# MainBoard_v5.net
KiCad netlist of a schematic drawn in EAGLE
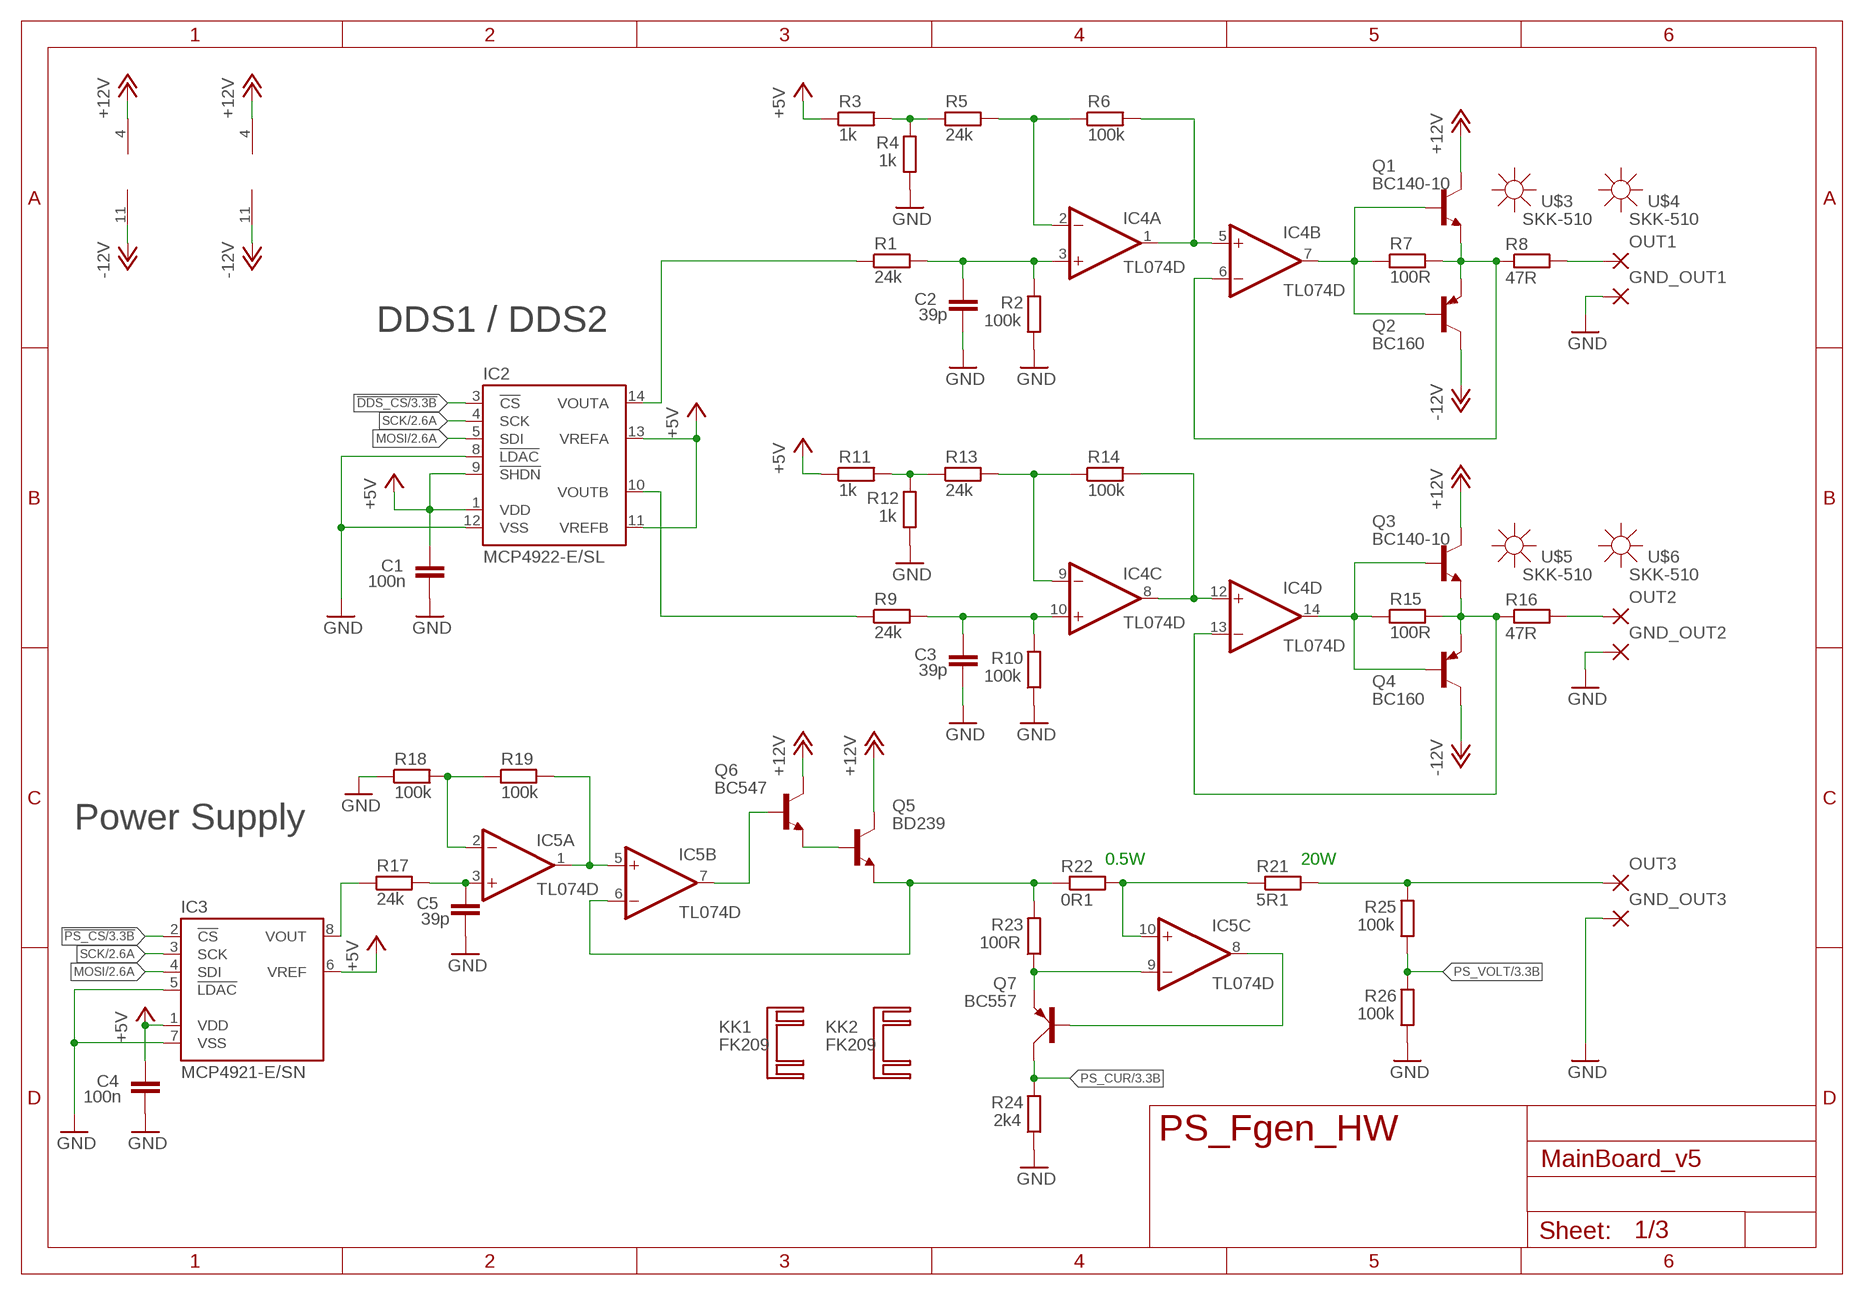
[diagram p0: schematic, sheet 1]
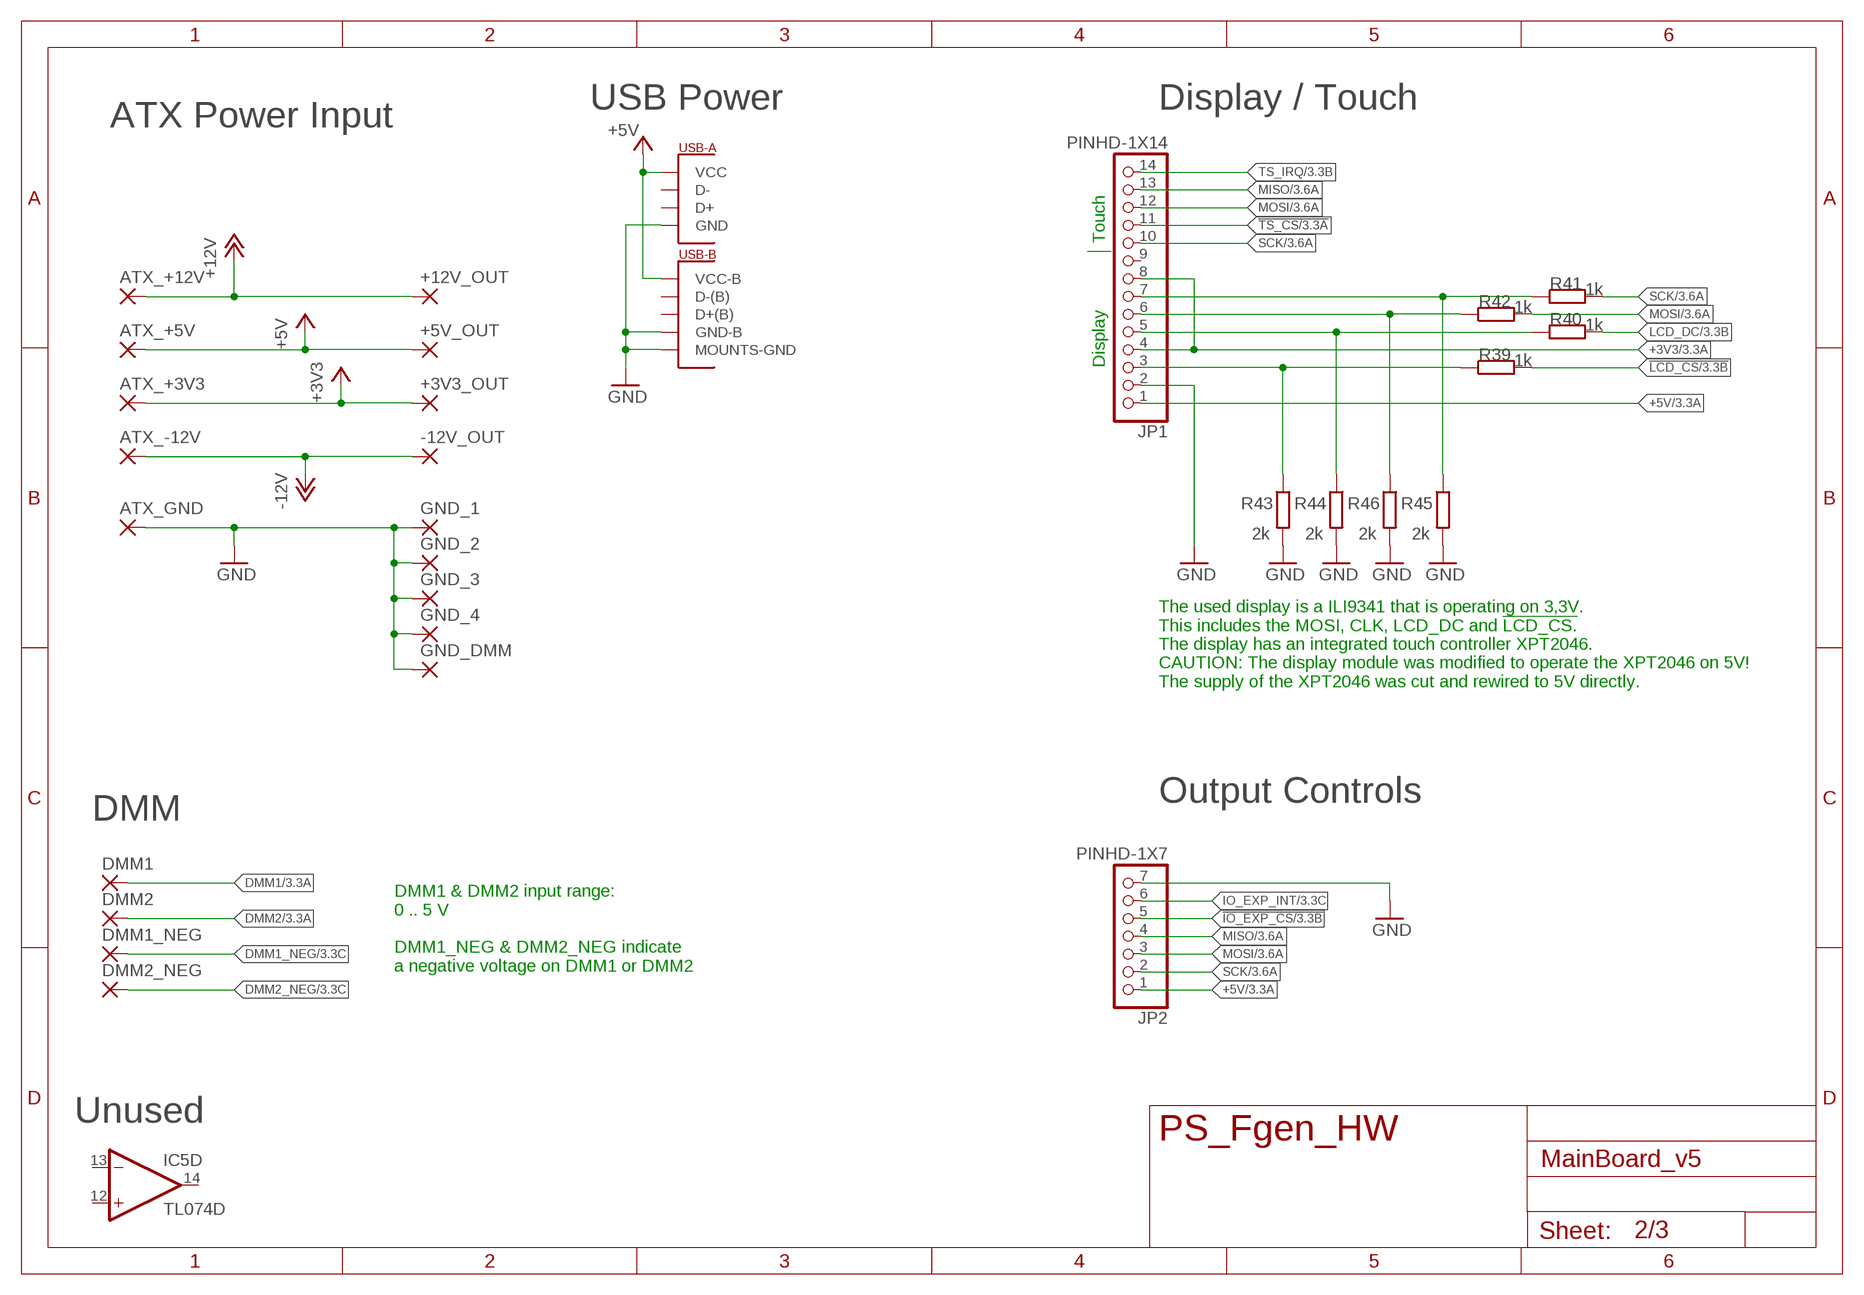
[diagram p1: schematic, sheet 2]
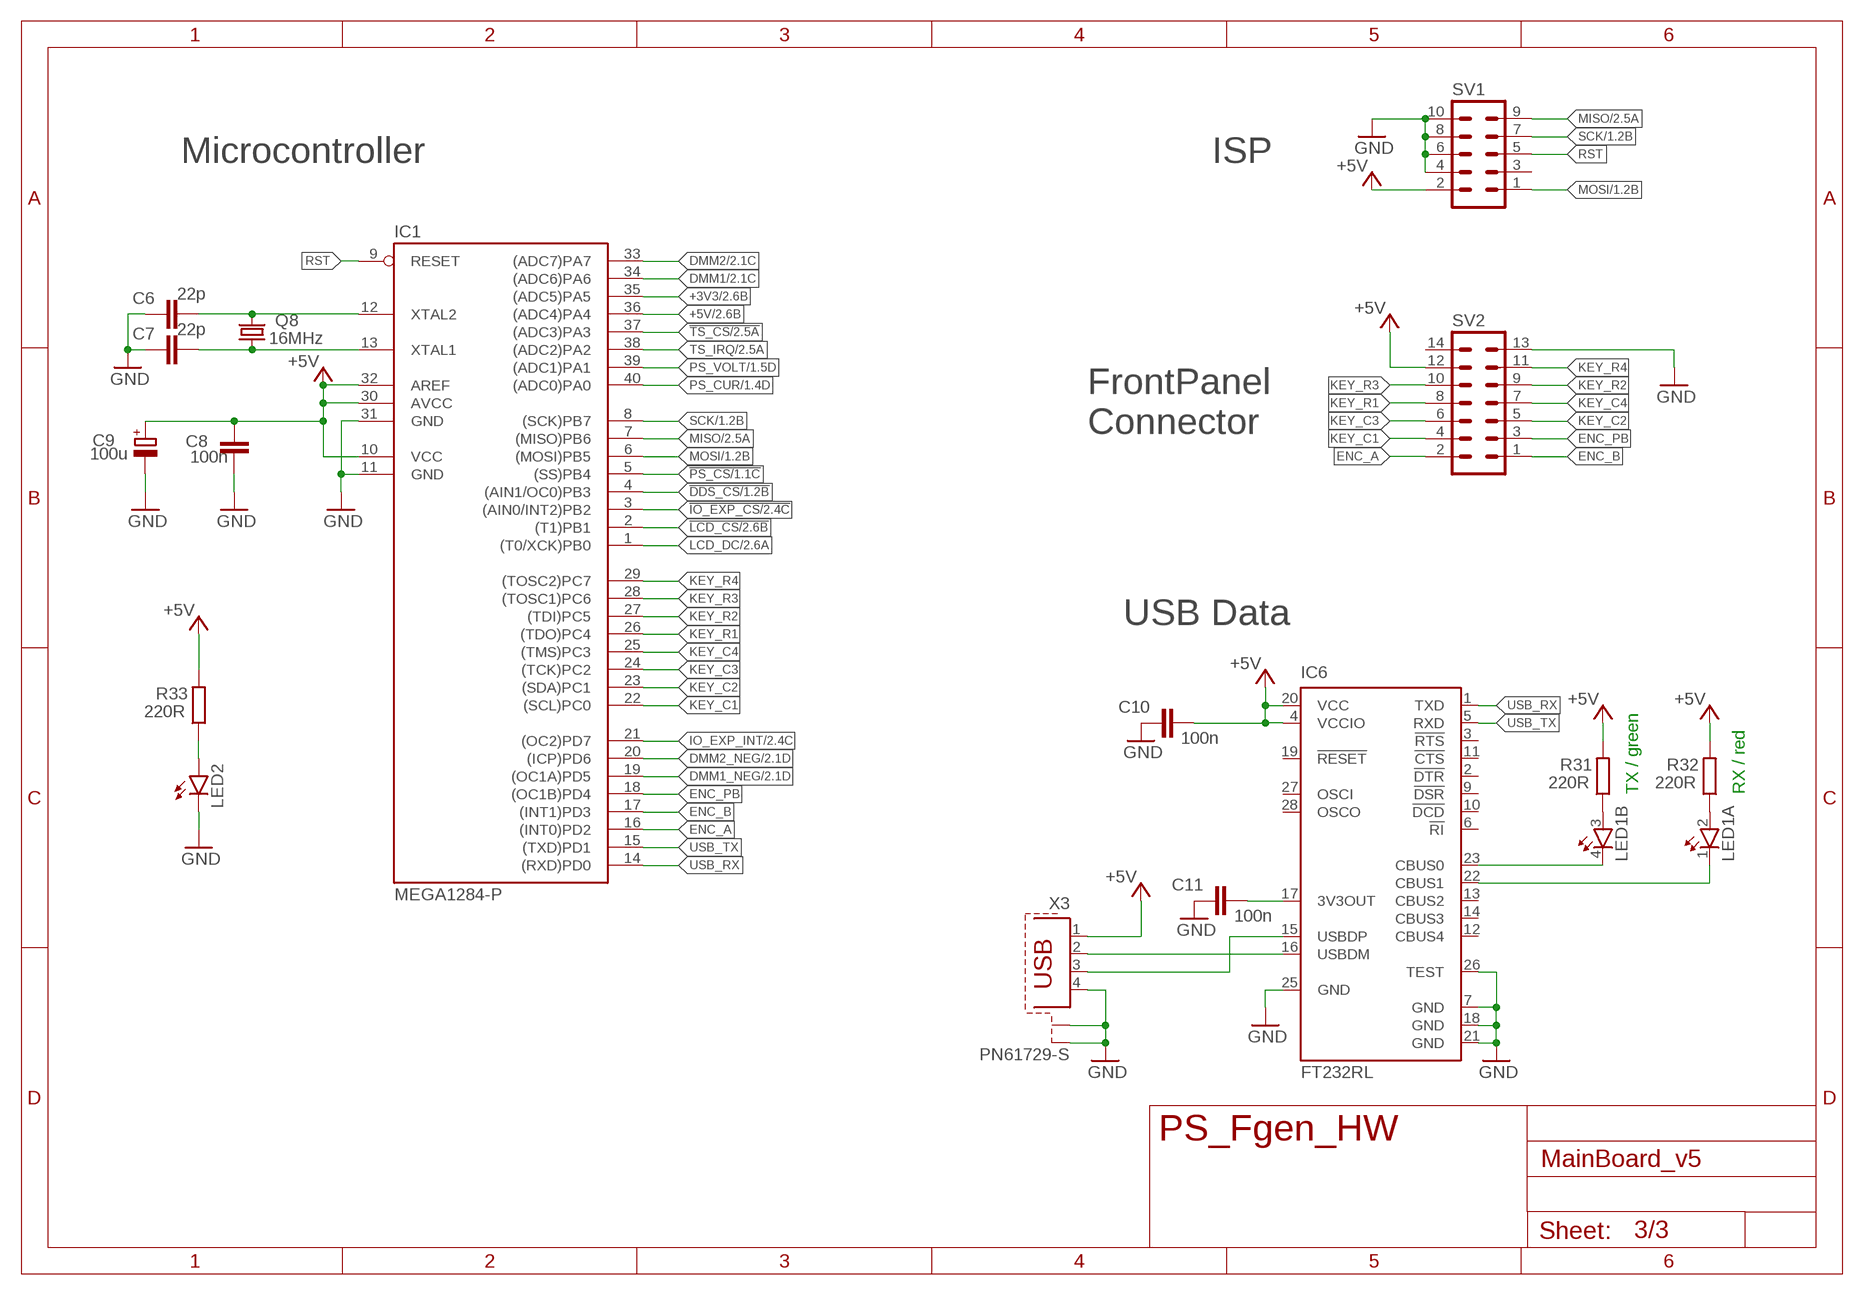
[diagram p2: schematic, sheet 3]

(export (version "E")
  (design (tool "Eeschema 10.0.6"))
  (components
    (comp (ref "C6")
      (value "22p")
      (footprint "eagle-import:C0805")
      (libsource (lib "eagle-import") (part "C-EUC0805"))
    )
    (comp (ref "C7")
      (value "22p")
      (footprint "eagle-import:C0805")
      (libsource (lib "eagle-import") (part "C-EUC0805"))
    )
    (comp (ref "C8")
      (value "100n")
      (footprint "eagle-import:C0805")
      (libsource (lib "eagle-import") (part "C-EUC0805"))
    )
    (comp (ref "C9")
      (value "100u")
      (footprint "eagle-import:PANASONIC_D")
      (libsource (lib "eagle-import") (part "CPOL-EUD"))
    )
    (comp (ref "C10")
      (value "100n")
      (footprint "eagle-import:C0805")
      (libsource (lib "eagle-import") (part "C-EUC0805"))
    )
    (comp (ref "C11")
      (value "100n")
      (footprint "eagle-import:C0805")
      (libsource (lib "eagle-import") (part "C-EUC0805"))
    )
    (comp (ref "IC1")
      (value "MEGA1284-P")
      (footprint "eagle-import:DIL40")
      (fields (field (name "MPN") "ATMEGA16-16PU"))
      (libsource (lib "eagle-import") (part "MEGA16-P"))
    )
    (comp (ref "IC6")
      (value "FT232RL")
      (footprint "eagle-import:SSOP28")
      (libsource (lib "eagle-import") (part "FT232RL"))
    )
    (comp (ref "LED1")
      (value "TOPLED-2--")
      (footprint "eagle-import:P-LCC-4-2")
      (libsource (lib "eagle-import") (part "TOPLED-2--"))
    )
    (comp (ref "LED2")
      (value "LEDCHIP-LED0805")
      (footprint "eagle-import:CHIP-LED0805")
      (libsource (lib "eagle-import") (part "LEDCHIP-LED0805"))
    )
    (comp (ref "Q8")
      (value "16MHz")
      (footprint "eagle-import:HC49_S")
      (libsource (lib "eagle-import") (part "CRYSTALHC49S"))
    )
    (comp (ref "R31")
      (value "220R")
      (footprint "eagle-import:R0805")
      (libsource (lib "eagle-import") (part "R-EU_R0805"))
    )
    (comp (ref "R32")
      (value "220R")
      (footprint "eagle-import:R0805")
      (libsource (lib "eagle-import") (part "R-EU_R0805"))
    )
    (comp (ref "R33")
      (value "220R")
      (footprint "eagle-import:R0805")
      (libsource (lib "eagle-import") (part "R-EU_R0805"))
    )
    (comp (ref "SV1")
      (value "ML10")
      (footprint "eagle-import:ML10")
      (libsource (lib "eagle-import") (part "ML10"))
    )
    (comp (ref "SV2")
      (value "ML14")
      (footprint "eagle-import:ML14")
      (libsource (lib "eagle-import") (part "ML14"))
    )
    (comp (ref "X3")
      (value "PN61729-S")
      (footprint "eagle-import:PN61729-S")
      (libsource (lib "eagle-import") (part "PN61729-S"))
    )
    (comp (ref "C1")
      (value "100n")
      (footprint "eagle-import:C0805")
      (libsource (lib "eagle-import") (part "C-EUC0805"))
    )
    (comp (ref "C2")
      (value "39p")
      (footprint "eagle-import:C0805")
      (libsource (lib "eagle-import") (part "C-EUC0805"))
    )
    (comp (ref "C3")
      (value "39p")
      (footprint "eagle-import:C0805")
      (libsource (lib "eagle-import") (part "C-EUC0805"))
    )
    (comp (ref "C4")
      (value "100n")
      (footprint "eagle-import:C0805")
      (libsource (lib "eagle-import") (part "C-EUC0805"))
    )
    (comp (ref "C5")
      (value "39p")
      (footprint "eagle-import:C0805")
      (libsource (lib "eagle-import") (part "C-EUC0805"))
    )
    (comp (ref "GND_OUT1")
      (value "2,54/1,0")
      (footprint "eagle-import:2,54_1,0")
      (libsource (lib "eagle-import") (part "2,54/1,0"))
    )
    (comp (ref "GND_OUT2")
      (value "2,54/1,0")
      (footprint "eagle-import:2,54_1,0")
      (libsource (lib "eagle-import") (part "2,54/1,0"))
    )
    (comp (ref "GND_OUT3")
      (value "2,54/1,0")
      (footprint "eagle-import:2,54_1,0")
      (libsource (lib "eagle-import") (part "2,54/1,0"))
    )
    (comp (ref "IC2")
      (value "MCP4922-E/SL")
      (footprint "eagle-import:SO14")
      (libsource (lib "eagle-import") (part "MCP4922-E/SL"))
    )
    (comp (ref "IC3")
      (value "MCP4921-E/SN")
      (footprint "eagle-import:SO08")
      (libsource (lib "eagle-import") (part "MCP4921-E/SN"))
    )
    (comp (ref "IC4")
      (value "TL074D")
      (footprint "eagle-import:SO14")
      (libsource (lib "eagle-import") (part "TL074D"))
    )
    (comp (ref "IC5")
      (value "TL074D")
      (footprint "eagle-import:SO14")
      (libsource (lib "eagle-import") (part "TL074D"))
    )
    (comp (ref "KK1")
      (value "FK209")
      (footprint "eagle-import:FK209")
      (libsource (lib "eagle-import") (part "FK209"))
    )
    (comp (ref "KK2")
      (value "FK209")
      (footprint "eagle-import:FK209")
      (libsource (lib "eagle-import") (part "FK209"))
    )
    (comp (ref "OUT1")
      (value "2,54/1,0")
      (footprint "eagle-import:2,54_1,0")
      (libsource (lib "eagle-import") (part "2,54/1,0"))
    )
    (comp (ref "OUT2")
      (value "2,54/1,0")
      (footprint "eagle-import:2,54_1,0")
      (libsource (lib "eagle-import") (part "2,54/1,0"))
    )
    (comp (ref "OUT3")
      (value "2,54/1,0")
      (footprint "eagle-import:2,54_1,0")
      (libsource (lib "eagle-import") (part "2,54/1,0"))
    )
    (comp (ref "Q1")
      (value "BC140-10")
      (footprint "eagle-import:TO39")
      (libsource (lib "eagle-import") (part "BC140-10"))
    )
    (comp (ref "Q2")
      (value "BC160")
      (footprint "eagle-import:TO39")
      (libsource (lib "eagle-import") (part "BC160"))
    )
    (comp (ref "Q3")
      (value "BC140-10")
      (footprint "eagle-import:TO39")
      (libsource (lib "eagle-import") (part "BC140-10"))
    )
    (comp (ref "Q4")
      (value "BC160")
      (footprint "eagle-import:TO39")
      (libsource (lib "eagle-import") (part "BC160"))
    )
    (comp (ref "Q5")
      (value "BD239")
      (footprint "eagle-import:CB-274")
      (libsource (lib "eagle-import") (part "BD239TO220BV"))
    )
    (comp (ref "Q6")
      (value "BC547")
      (footprint "eagle-import:TO92")
      (libsource (lib "eagle-import") (part "BC547"))
    )
    (comp (ref "Q7")
      (value "BC557")
      (footprint "eagle-import:SOT54A")
      (libsource (lib "eagle-import") (part "BC557"))
    )
    (comp (ref "R1")
      (value "24k")
      (footprint "eagle-import:R0805")
      (libsource (lib "eagle-import") (part "R-EU_R0805"))
    )
    (comp (ref "R2")
      (value "100k")
      (footprint "eagle-import:R0805")
      (libsource (lib "eagle-import") (part "R-EU_R0805"))
    )
    (comp (ref "R3")
      (value "1k")
      (footprint "eagle-import:R0805")
      (libsource (lib "eagle-import") (part "R-EU_R0805"))
    )
    (comp (ref "R4")
      (value "1k")
      (footprint "eagle-import:R0805")
      (libsource (lib "eagle-import") (part "R-EU_R0805"))
    )
    (comp (ref "R5")
      (value "24k")
      (footprint "eagle-import:R0805")
      (libsource (lib "eagle-import") (part "R-EU_R0805"))
    )
    (comp (ref "R6")
      (value "100k")
      (footprint "eagle-import:R0805")
      (libsource (lib "eagle-import") (part "R-EU_R0805"))
    )
    (comp (ref "R7")
      (value "100R")
      (footprint "eagle-import:R0805")
      (libsource (lib "eagle-import") (part "R-EU_R0805"))
    )
    (comp (ref "R8")
      (value "47R")
      (footprint "eagle-import:0411_15")
      (libsource (lib "eagle-import") (part "R-EU_0411/15"))
    )
    (comp (ref "R9")
      (value "24k")
      (footprint "eagle-import:R0805")
      (libsource (lib "eagle-import") (part "R-EU_R0805"))
    )
    (comp (ref "R10")
      (value "100k")
      (footprint "eagle-import:R0805")
      (libsource (lib "eagle-import") (part "R-EU_R0805"))
    )
    (comp (ref "R11")
      (value "1k")
      (footprint "eagle-import:R0805")
      (libsource (lib "eagle-import") (part "R-EU_R0805"))
    )
    (comp (ref "R12")
      (value "1k")
      (footprint "eagle-import:R0805")
      (libsource (lib "eagle-import") (part "R-EU_R0805"))
    )
    (comp (ref "R13")
      (value "24k")
      (footprint "eagle-import:R0805")
      (libsource (lib "eagle-import") (part "R-EU_R0805"))
    )
    (comp (ref "R14")
      (value "100k")
      (footprint "eagle-import:R0805")
      (libsource (lib "eagle-import") (part "R-EU_R0805"))
    )
    (comp (ref "R15")
      (value "100R")
      (footprint "eagle-import:R0805")
      (libsource (lib "eagle-import") (part "R-EU_R0805"))
    )
    (comp (ref "R16")
      (value "47R")
      (footprint "eagle-import:0411_15")
      (libsource (lib "eagle-import") (part "R-EU_0411/15"))
    )
    (comp (ref "R17")
      (value "24k")
      (footprint "eagle-import:R0805")
      (libsource (lib "eagle-import") (part "R-EU_R0805"))
    )
    (comp (ref "R18")
      (value "100k")
      (footprint "eagle-import:R0805")
      (libsource (lib "eagle-import") (part "R-EU_R0805"))
    )
    (comp (ref "R19")
      (value "100k")
      (footprint "eagle-import:R0805")
      (libsource (lib "eagle-import") (part "R-EU_R0805"))
    )
    (comp (ref "R21")
      (value "5R1")
      (footprint "eagle-import:0411_15")
      (libsource (lib "eagle-import") (part "R-EU_0411/15"))
    )
    (comp (ref "R22")
      (value "0R1")
      (footprint "eagle-import:0411_15")
      (libsource (lib "eagle-import") (part "R-EU_0411/15"))
    )
    (comp (ref "R23")
      (value "100R")
      (footprint "eagle-import:R0805")
      (libsource (lib "eagle-import") (part "R-EU_R0805"))
    )
    (comp (ref "R24")
      (value "2k4")
      (footprint "eagle-import:R0805")
      (libsource (lib "eagle-import") (part "R-EU_R0805"))
    )
    (comp (ref "R25")
      (value "100k")
      (footprint "eagle-import:R0805")
      (libsource (lib "eagle-import") (part "R-EU_R0805"))
    )
    (comp (ref "R26")
      (value "100k")
      (footprint "eagle-import:R0805")
      (libsource (lib "eagle-import") (part "R-EU_R0805"))
    )
    (comp (ref "U$3")
      (value "SKK-510")
      (footprint "eagle-import:SKK")
      (libsource (lib "eagle-import") (part "SKK-510"))
    )
    (comp (ref "U$4")
      (value "SKK-510")
      (footprint "eagle-import:SKK")
      (libsource (lib "eagle-import") (part "SKK-510"))
    )
    (comp (ref "U$5")
      (value "SKK-510")
      (footprint "eagle-import:SKK")
      (libsource (lib "eagle-import") (part "SKK-510"))
    )
    (comp (ref "U$6")
      (value "SKK-510")
      (footprint "eagle-import:SKK")
      (libsource (lib "eagle-import") (part "SKK-510"))
    )
    (comp (ref "+3V3_OUT")
      (value "2,54/1,0")
      (footprint "eagle-import:2,54_1,0")
      (libsource (lib "eagle-import") (part "2,54/1,0"))
    )
    (comp (ref "+5V_OUT")
      (value "2,54/1,0")
      (footprint "eagle-import:2,54_1,0")
      (libsource (lib "eagle-import") (part "2,54/1,0"))
    )
    (comp (ref "+12V_OUT")
      (value "2,54/1,0")
      (footprint "eagle-import:2,54_1,0")
      (libsource (lib "eagle-import") (part "2,54/1,0"))
    )
    (comp (ref "-12V_OUT")
      (value "2,54/1,0")
      (footprint "eagle-import:2,54_1,0")
      (libsource (lib "eagle-import") (part "2,54/1,0"))
    )
    (comp (ref "ATX_+3V3")
      (value "2,54/1,0")
      (footprint "eagle-import:2,54_1,0")
      (libsource (lib "eagle-import") (part "2,54/1,0"))
    )
    (comp (ref "ATX_+5V")
      (value "2,54/1,0")
      (footprint "eagle-import:2,54_1,0")
      (libsource (lib "eagle-import") (part "2,54/1,0"))
    )
    (comp (ref "ATX_+12V")
      (value "2,54/1,0")
      (footprint "eagle-import:2,54_1,0")
      (libsource (lib "eagle-import") (part "2,54/1,0"))
    )
    (comp (ref "ATX_-12V")
      (value "2,54/1,0")
      (footprint "eagle-import:2,54_1,0")
      (libsource (lib "eagle-import") (part "2,54/1,0"))
    )
    (comp (ref "ATX_GND")
      (value "2,54/1,0")
      (footprint "eagle-import:2,54_1,0")
      (libsource (lib "eagle-import") (part "2,54/1,0"))
    )
    (comp (ref "DMM1")
      (value "2,54/1,0")
      (footprint "eagle-import:2,54_1,0")
      (libsource (lib "eagle-import") (part "2,54/1,0"))
    )
    (comp (ref "DMM1_NEG")
      (value "2,54/1,0")
      (footprint "eagle-import:2,54_1,0")
      (libsource (lib "eagle-import") (part "2,54/1,0"))
    )
    (comp (ref "DMM2")
      (value "2,54/1,0")
      (footprint "eagle-import:2,54_1,0")
      (libsource (lib "eagle-import") (part "2,54/1,0"))
    )
    (comp (ref "DMM2_NEG")
      (value "2,54/1,0")
      (footprint "eagle-import:2,54_1,0")
      (libsource (lib "eagle-import") (part "2,54/1,0"))
    )
    (comp (ref "GND_1")
      (value "2,54/1,0")
      (footprint "eagle-import:2,54_1,0")
      (libsource (lib "eagle-import") (part "2,54/1,0"))
    )
    (comp (ref "GND_2")
      (value "2,54/1,0")
      (footprint "eagle-import:2,54_1,0")
      (libsource (lib "eagle-import") (part "2,54/1,0"))
    )
    (comp (ref "GND_3")
      (value "2,54/1,0")
      (footprint "eagle-import:2,54_1,0")
      (libsource (lib "eagle-import") (part "2,54/1,0"))
    )
    (comp (ref "GND_4")
      (value "2,54/1,0")
      (footprint "eagle-import:2,54_1,0")
      (libsource (lib "eagle-import") (part "2,54/1,0"))
    )
    (comp (ref "GND_DMM")
      (value "2,54/1,0")
      (footprint "eagle-import:2,54_1,0")
      (libsource (lib "eagle-import") (part "2,54/1,0"))
    )
    (comp (ref "JP1")
      (value "PINHD-1X14")
      (footprint "eagle-import:1X14")
      (libsource (lib "eagle-import") (part "PINHD-1X14"))
    )
    (comp (ref "JP2")
      (value "PINHD-1X7")
      (footprint "eagle-import:1X07")
      (libsource (lib "eagle-import") (part "PINHD-1X7"))
    )
    (comp (ref "R39")
      (value "1k")
      (footprint "eagle-import:R0805")
      (libsource (lib "eagle-import") (part "R-EU_R0805"))
    )
    (comp (ref "R40")
      (value "1k")
      (footprint "eagle-import:R0805")
      (libsource (lib "eagle-import") (part "R-EU_R0805"))
    )
    (comp (ref "R41")
      (value "1k")
      (footprint "eagle-import:R0805")
      (libsource (lib "eagle-import") (part "R-EU_R0805"))
    )
    (comp (ref "R42")
      (value "1k")
      (footprint "eagle-import:R0805")
      (libsource (lib "eagle-import") (part "R-EU_R0805"))
    )
    (comp (ref "R43")
      (value "2k")
      (footprint "eagle-import:R0805")
      (libsource (lib "eagle-import") (part "R-EU_R0805"))
    )
    (comp (ref "R44")
      (value "2k")
      (footprint "eagle-import:R0805")
      (libsource (lib "eagle-import") (part "R-EU_R0805"))
    )
    (comp (ref "R45")
      (value "2k")
      (footprint "eagle-import:R0805")
      (libsource (lib "eagle-import") (part "R-EU_R0805"))
    )
    (comp (ref "R46")
      (value "2k")
      (footprint "eagle-import:R0805")
      (libsource (lib "eagle-import") (part "R-EU_R0805"))
    )
    (comp (ref "U$2")
      (value "DUAL-PORT-USB-REC")
      (footprint "eagle-import:DUAL-PORT-USB")
      (libsource (lib "eagle-import") (part "DUAL-PORT-USB-REC"))
    )
  )
  (nets
    (net (code "1") (name "+3V3") (class "Default")
      (node (ref "+3V3_OUT") (pin "1") (pinfunction "P_1") (pintype "passive"))
      (node (ref "ATX_+3V3") (pin "1") (pinfunction "P_1") (pintype "passive"))
      (node (ref "IC1") (pin "35") (pinfunction "(ADC5)PA5_35") (pintype "bidirectional"))
      (node (ref "JP1") (pin "4") (pinfunction "4_4") (pintype "passive"))
      (node (ref "JP1") (pin "8") (pinfunction "8_8") (pintype "passive"))
    )
    (net (code "2") (name "+5V") (class "Default")
      (node (ref "+5V_OUT") (pin "1") (pinfunction "P_1") (pintype "passive"))
      (node (ref "ATX_+5V") (pin "1") (pinfunction "P_1") (pintype "passive"))
      (node (ref "C1") (pin "2") (pinfunction "2_2") (pintype "passive"))
      (node (ref "C10") (pin "1") (pinfunction "1_1") (pintype "passive"))
      (node (ref "C4") (pin "2") (pinfunction "2_2") (pintype "passive"))
      (node (ref "C8") (pin "2") (pinfunction "2_2") (pintype "passive"))
      (node (ref "C9") (pin "+") (pinfunction "+_+") (pintype "passive"))
      (node (ref "IC1") (pin "10") (pinfunction "VCC_10") (pintype "power_in"))
      (node (ref "IC1") (pin "30") (pinfunction "AVCC_30") (pintype "power_in"))
      (node (ref "IC1") (pin "32") (pinfunction "AREF_32") (pintype "passive"))
      (node (ref "IC1") (pin "36") (pinfunction "(ADC4)PA4_36") (pintype "bidirectional"))
      (node (ref "IC2") (pin "1") (pinfunction "VDD_1") (pintype "power_in"))
      (node (ref "IC2") (pin "11") (pinfunction "VREFB_11") (pintype "input"))
      (node (ref "IC2") (pin "13") (pinfunction "VREFA_13") (pintype "input"))
      (node (ref "IC2") (pin "9") (pinfunction "~{SHDN}_9") (pintype "input"))
      (node (ref "IC3") (pin "1") (pinfunction "VDD_1") (pintype "power_in"))
      (node (ref "IC3") (pin "6") (pinfunction "VREF_6") (pintype "input"))
      (node (ref "IC6") (pin "20") (pinfunction "VCC_20") (pintype "power_in"))
      (node (ref "IC6") (pin "4") (pinfunction "VCCIO_4") (pintype "power_in"))
      (node (ref "JP1") (pin "1") (pinfunction "1_1") (pintype "passive"))
      (node (ref "JP2") (pin "1") (pinfunction "1_1") (pintype "passive"))
      (node (ref "R11") (pin "1") (pinfunction "1_1") (pintype "passive"))
      (node (ref "R3") (pin "1") (pinfunction "1_1") (pintype "passive"))
      (node (ref "R31") (pin "2") (pinfunction "2_2") (pintype "passive"))
      (node (ref "R32") (pin "2") (pinfunction "2_2") (pintype "passive"))
      (node (ref "R33") (pin "2") (pinfunction "2_2") (pintype "passive"))
      (node (ref "SV1") (pin "2") (pinfunction "2_2") (pintype "passive"))
      (node (ref "SV2") (pin "12") (pinfunction "12_12") (pintype "passive"))
      (node (ref "U$2") (pin "P$10") (pinfunction "VCC-B_P$10") (pintype "power_in"))
      (node (ref "U$2") (pin "P$12") (pinfunction "VCC_P$12") (pintype "power_in"))
      (node (ref "X3") (pin "1") (pinfunction "1_1") (pintype "passive"))
    )
    (net (code "3") (name "+12V") (class "Default")
      (node (ref "+12V_OUT") (pin "1") (pinfunction "P_1") (pintype "passive"))
      (node (ref "ATX_+12V") (pin "1") (pinfunction "P_1") (pintype "passive"))
      (node (ref "IC4") (pin "4") (pinfunction "V+_4") (pintype "power_in"))
      (node (ref "IC5") (pin "4") (pinfunction "V+_4") (pintype "power_in"))
      (node (ref "Q1") (pin "3") (pinfunction "C_3") (pintype "passive"))
      (node (ref "Q3") (pin "3") (pinfunction "C_3") (pintype "passive"))
      (node (ref "Q5") (pin "T2") (pinfunction "C_T2") (pintype "passive"))
      (node (ref "Q6") (pin "3") (pinfunction "C_3") (pintype "passive"))
    )
    (net (code "4") (name "-12V") (class "Default")
      (node (ref "-12V_OUT") (pin "1") (pinfunction "P_1") (pintype "passive"))
      (node (ref "ATX_-12V") (pin "1") (pinfunction "P_1") (pintype "passive"))
      (node (ref "IC4") (pin "11") (pinfunction "V-_11") (pintype "power_in"))
      (node (ref "IC5") (pin "11") (pinfunction "V-_11") (pintype "power_in"))
      (node (ref "Q2") (pin "3") (pinfunction "C_3") (pintype "passive"))
      (node (ref "Q4") (pin "3") (pinfunction "C_3") (pintype "passive"))
    )
    (net (code "5") (name "DMM1") (class "Default")
      (node (ref "DMM1") (pin "1") (pinfunction "P_1") (pintype "passive"))
      (node (ref "IC1") (pin "34") (pinfunction "(ADC6)PA6_34") (pintype "bidirectional"))
    )
    (net (code "6") (name "DMM1_NEG") (class "Default")
      (node (ref "DMM1_NEG") (pin "1") (pinfunction "P_1") (pintype "passive"))
      (node (ref "IC1") (pin "19") (pinfunction "(OC1A)PD5_19") (pintype "bidirectional"))
    )
    (net (code "7") (name "DMM2") (class "Default")
      (node (ref "DMM2") (pin "1") (pinfunction "P_1") (pintype "passive"))
      (node (ref "IC1") (pin "33") (pinfunction "(ADC7)PA7_33") (pintype "bidirectional"))
    )
    (net (code "8") (name "DMM2_NEG") (class "Default")
      (node (ref "DMM2_NEG") (pin "1") (pinfunction "P_1") (pintype "passive"))
      (node (ref "IC1") (pin "20") (pinfunction "(ICP)PD6_20") (pintype "bidirectional"))
    )
    (net (code "9") (name "ENC_A") (class "Default")
      (node (ref "IC1") (pin "16") (pinfunction "(INT0)PD2_16") (pintype "bidirectional"))
      (node (ref "SV2") (pin "2") (pinfunction "2_2") (pintype "passive"))
    )
    (net (code "10") (name "ENC_B") (class "Default")
      (node (ref "IC1") (pin "17") (pinfunction "(INT1)PD3_17") (pintype "bidirectional"))
      (node (ref "SV2") (pin "1") (pinfunction "1_1") (pintype "passive"))
    )
    (net (code "11") (name "ENC_PB") (class "Default")
      (node (ref "IC1") (pin "18") (pinfunction "(OC1B)PD4_18") (pintype "bidirectional"))
      (node (ref "SV2") (pin "3") (pinfunction "3_3") (pintype "passive"))
    )
    (net (code "12") (name "GND") (class "Default")
      (node (ref "ATX_GND") (pin "1") (pinfunction "P_1") (pintype "passive"))
      (node (ref "C1") (pin "1") (pinfunction "1_1") (pintype "passive"))
      (node (ref "C10") (pin "2") (pinfunction "2_2") (pintype "passive"))
      (node (ref "C11") (pin "2") (pinfunction "2_2") (pintype "passive"))
      (node (ref "C2") (pin "1") (pinfunction "1_1") (pintype "passive"))
      (node (ref "C3") (pin "1") (pinfunction "1_1") (pintype "passive"))
      (node (ref "C4") (pin "1") (pinfunction "1_1") (pintype "passive"))
      (node (ref "C5") (pin "1") (pinfunction "1_1") (pintype "passive"))
      (node (ref "C6") (pin "2") (pinfunction "2_2") (pintype "passive"))
      (node (ref "C7") (pin "2") (pinfunction "2_2") (pintype "passive"))
      (node (ref "C8") (pin "1") (pinfunction "1_1") (pintype "passive"))
      (node (ref "C9") (pin "-") (pinfunction "-_-") (pintype "passive"))
      (node (ref "GND_1") (pin "1") (pinfunction "P_1") (pintype "passive"))
      (node (ref "GND_2") (pin "1") (pinfunction "P_1") (pintype "passive"))
      (node (ref "GND_3") (pin "1") (pinfunction "P_1") (pintype "passive"))
      (node (ref "GND_4") (pin "1") (pinfunction "P_1") (pintype "passive"))
      (node (ref "GND_DMM") (pin "1") (pinfunction "P_1") (pintype "passive"))
      (node (ref "GND_OUT1") (pin "1") (pinfunction "P_1") (pintype "passive"))
      (node (ref "GND_OUT2") (pin "1") (pinfunction "P_1") (pintype "passive"))
      (node (ref "GND_OUT3") (pin "1") (pinfunction "P_1") (pintype "passive"))
      (node (ref "IC1") (pin "11") (pinfunction "GND_11") (pintype "power_in"))
      (node (ref "IC1") (pin "31") (pinfunction "GND_31") (pintype "power_in"))
      (node (ref "IC2") (pin "12") (pinfunction "VSS_12") (pintype "power_in"))
      (node (ref "IC2") (pin "8") (pinfunction "~{LDAC}_8") (pintype "input"))
      (node (ref "IC3") (pin "5") (pinfunction "~{LDAC}_5") (pintype "input"))
      (node (ref "IC3") (pin "7") (pinfunction "VSS_7") (pintype "power_in"))
      (node (ref "IC6") (pin "18") (pinfunction "GND_18") (pintype "power_in"))
      (node (ref "IC6") (pin "21") (pinfunction "GND_21") (pintype "power_in"))
      (node (ref "IC6") (pin "25") (pinfunction "GND_25") (pintype "power_in"))
      (node (ref "IC6") (pin "26") (pinfunction "TEST_26") (pintype "input"))
      (node (ref "IC6") (pin "7") (pinfunction "GND_7") (pintype "power_in"))
      (node (ref "JP1") (pin "2") (pinfunction "2_2") (pintype "passive"))
      (node (ref "JP2") (pin "7") (pinfunction "7_7") (pintype "passive"))
      (node (ref "LED2") (pin "C") (pinfunction "C_C") (pintype "passive"))
      (node (ref "R10") (pin "1") (pinfunction "1_1") (pintype "passive"))
      (node (ref "R12") (pin "1") (pinfunction "1_1") (pintype "passive"))
      (node (ref "R18") (pin "1") (pinfunction "1_1") (pintype "passive"))
      (node (ref "R2") (pin "1") (pinfunction "1_1") (pintype "passive"))
      (node (ref "R24") (pin "1") (pinfunction "1_1") (pintype "passive"))
      (node (ref "R26") (pin "1") (pinfunction "1_1") (pintype "passive"))
      (node (ref "R4") (pin "1") (pinfunction "1_1") (pintype "passive"))
      (node (ref "R43") (pin "2") (pinfunction "2_2") (pintype "passive"))
      (node (ref "R44") (pin "2") (pinfunction "2_2") (pintype "passive"))
      (node (ref "R45") (pin "2") (pinfunction "2_2") (pintype "passive"))
      (node (ref "R46") (pin "2") (pinfunction "2_2") (pintype "passive"))
      (node (ref "SV1") (pin "10") (pinfunction "10_10") (pintype "passive"))
      (node (ref "SV1") (pin "4") (pinfunction "4_4") (pintype "passive"))
      (node (ref "SV1") (pin "6") (pinfunction "6_6") (pintype "passive"))
      (node (ref "SV1") (pin "8") (pinfunction "8_8") (pintype "passive"))
      (node (ref "SV2") (pin "13") (pinfunction "13_13") (pintype "passive"))
      (node (ref "U$2") (pin "GND") (pinfunction "MOUNTS-GND_GND") (pintype "power_in"))
      (node (ref "U$2") (pin "P$11") (pinfunction "GND_P$11") (pintype "power_in"))
      (node (ref "U$2") (pin "P$2") (pinfunction "MOUNTS-GND_P$2") (pintype "power_in"))
      (node (ref "U$2") (pin "P$3") (pinfunction "MOUNTS-GND_P$3") (pintype "power_in"))
      (node (ref "U$2") (pin "P$4") (pinfunction "MOUNTS-GND_P$4") (pintype "power_in"))
      (node (ref "U$2") (pin "P$9") (pinfunction "GND-B_P$9") (pintype "power_in"))
      (node (ref "X3") (pin "4") (pinfunction "4_4") (pintype "passive"))
      (node (ref "X3") (pin "S1") (pinfunction "S1_S1") (pintype "passive"))
      (node (ref "X3") (pin "S2") (pinfunction "S2_S2") (pintype "passive"))
    )
    (net (code "13") (name "IO_EXP_INT") (class "Default")
      (node (ref "IC1") (pin "21") (pinfunction "(OC2)PD7_21") (pintype "bidirectional"))
      (node (ref "JP2") (pin "6") (pinfunction "6_6") (pintype "passive"))
    )
    (net (code "14") (name "KEY_C1") (class "Default")
      (node (ref "IC1") (pin "22") (pinfunction "(SCL)PC0_22") (pintype "bidirectional"))
      (node (ref "SV2") (pin "4") (pinfunction "4_4") (pintype "passive"))
    )
    (net (code "15") (name "KEY_C2") (class "Default")
      (node (ref "IC1") (pin "23") (pinfunction "(SDA)PC1_23") (pintype "bidirectional"))
      (node (ref "SV2") (pin "5") (pinfunction "5_5") (pintype "passive"))
    )
    (net (code "16") (name "KEY_C3") (class "Default")
      (node (ref "IC1") (pin "24") (pinfunction "(TCK)PC2_24") (pintype "bidirectional"))
      (node (ref "SV2") (pin "6") (pinfunction "6_6") (pintype "passive"))
    )
    (net (code "17") (name "KEY_C4") (class "Default")
      (node (ref "IC1") (pin "25") (pinfunction "(TMS)PC3_25") (pintype "bidirectional"))
      (node (ref "SV2") (pin "7") (pinfunction "7_7") (pintype "passive"))
    )
    (net (code "18") (name "KEY_R1") (class "Default")
      (node (ref "IC1") (pin "26") (pinfunction "(TDO)PC4_26") (pintype "bidirectional"))
      (node (ref "SV2") (pin "8") (pinfunction "8_8") (pintype "passive"))
    )
    (net (code "19") (name "KEY_R2") (class "Default")
      (node (ref "IC1") (pin "27") (pinfunction "(TDI)PC5_27") (pintype "bidirectional"))
      (node (ref "SV2") (pin "9") (pinfunction "9_9") (pintype "passive"))
    )
    (net (code "20") (name "KEY_R3") (class "Default")
      (node (ref "IC1") (pin "28") (pinfunction "(TOSC1)PC6_28") (pintype "bidirectional"))
      (node (ref "SV2") (pin "10") (pinfunction "10_10") (pintype "passive"))
    )
    (net (code "21") (name "KEY_R4") (class "Default")
      (node (ref "IC1") (pin "29") (pinfunction "(TOSC2)PC7_29") (pintype "bidirectional"))
      (node (ref "SV2") (pin "11") (pinfunction "11_11") (pintype "passive"))
    )
    (net (code "22") (name "LCD_DC") (class "Default")
      (node (ref "IC1") (pin "1") (pinfunction "(T0/XCK)PB0_1") (pintype "bidirectional"))
      (node (ref "R40") (pin "2") (pinfunction "2_2") (pintype "passive"))
    )
    (net (code "23") (name "MISO") (class "Default")
      (node (ref "IC1") (pin "7") (pinfunction "(MISO)PB6_7") (pintype "bidirectional"))
      (node (ref "JP1") (pin "13") (pinfunction "13_13") (pintype "passive"))
      (node (ref "JP2") (pin "4") (pinfunction "4_4") (pintype "passive"))
      (node (ref "SV1") (pin "9") (pinfunction "9_9") (pintype "passive"))
    )
    (net (code "24") (name "MOSI") (class "Default")
      (node (ref "IC1") (pin "6") (pinfunction "(MOSI)PB5_6") (pintype "bidirectional"))
      (node (ref "IC2") (pin "5") (pinfunction "SDI_5") (pintype "input"))
      (node (ref "IC3") (pin "4") (pinfunction "SDI_4") (pintype "input"))
      (node (ref "JP1") (pin "12") (pinfunction "12_12") (pintype "passive"))
      (node (ref "JP2") (pin "3") (pinfunction "3_3") (pintype "passive"))
      (node (ref "R42") (pin "2") (pinfunction "2_2") (pintype "passive"))
      (node (ref "SV1") (pin "1") (pinfunction "1_1") (pintype "passive"))
    )
    (net (code "25") (name "Net-(IC1-XTAL1)") (class "Default")
      (node (ref "C7") (pin "1") (pinfunction "1_1") (pintype "passive"))
      (node (ref "IC1") (pin "13") (pinfunction "XTAL1_13") (pintype "bidirectional"))
      (node (ref "Q8") (pin "1") (pinfunction "1_1") (pintype "passive"))
    )
    (net (code "26") (name "Net-(IC1-XTAL2)") (class "Default")
      (node (ref "C6") (pin "1") (pinfunction "1_1") (pintype "passive"))
      (node (ref "IC1") (pin "12") (pinfunction "XTAL2_12") (pintype "bidirectional"))
      (node (ref "Q8") (pin "2") (pinfunction "2_2") (pintype "passive"))
    )
    (net (code "27") (name "Net-(IC2-VOUTA)") (class "Default")
      (node (ref "IC2") (pin "14") (pinfunction "VOUTA_14") (pintype "output"))
      (node (ref "R1") (pin "1") (pinfunction "1_1") (pintype "passive"))
    )
    (net (code "28") (name "Net-(IC2-VOUTB)") (class "Default")
      (node (ref "IC2") (pin "10") (pinfunction "VOUTB_10") (pintype "output"))
      (node (ref "R9") (pin "1") (pinfunction "1_1") (pintype "passive"))
    )
    (net (code "29") (name "Net-(IC3-VOUT)") (class "Default")
      (node (ref "IC3") (pin "8") (pinfunction "VOUT_8") (pintype "output"))
      (node (ref "R17") (pin "1") (pinfunction "1_1") (pintype "passive"))
    )
    (net (code "30") (name "Net-(IC4A-+IN)") (class "Default")
      (node (ref "C2") (pin "2") (pinfunction "2_2") (pintype "passive"))
      (node (ref "IC4") (pin "3") (pinfunction "+IN_3") (pintype "input"))
      (node (ref "R1") (pin "2") (pinfunction "2_2") (pintype "passive"))
      (node (ref "R2") (pin "2") (pinfunction "2_2") (pintype "passive"))
    )
    (net (code "31") (name "Net-(IC4A--IN)") (class "Default")
      (node (ref "IC4") (pin "2") (pinfunction "-IN_2") (pintype "input"))
      (node (ref "R5") (pin "2") (pinfunction "2_2") (pintype "passive"))
      (node (ref "R6") (pin "1") (pinfunction "1_1") (pintype "passive"))
    )
    (net (code "32") (name "Net-(IC4A-OUT)") (class "Default")
      (node (ref "IC4") (pin "1") (pinfunction "OUT_1") (pintype "output"))
      (node (ref "IC4") (pin "5") (pinfunction "+IN_5") (pintype "input"))
      (node (ref "R6") (pin "2") (pinfunction "2_2") (pintype "passive"))
    )
    (net (code "33") (name "Net-(IC4B--IN)") (class "Default")
      (node (ref "IC4") (pin "6") (pinfunction "-IN_6") (pintype "input"))
      (node (ref "Q1") (pin "1") (pinfunction "E_1") (pintype "passive"))
      (node (ref "Q2") (pin "1") (pinfunction "E_1") (pintype "passive"))
      (node (ref "R7") (pin "2") (pinfunction "2_2") (pintype "passive"))
      (node (ref "R8") (pin "1") (pinfunction "1_1") (pintype "passive"))
    )
    (net (code "34") (name "Net-(IC4B-OUT)") (class "Default")
      (node (ref "IC4") (pin "7") (pinfunction "OUT_7") (pintype "output"))
      (node (ref "Q1") (pin "2") (pinfunction "B_2") (pintype "passive"))
      (node (ref "Q2") (pin "2") (pinfunction "B_2") (pintype "passive"))
      (node (ref "R7") (pin "1") (pinfunction "1_1") (pintype "passive"))
    )
    (net (code "35") (name "Net-(IC4C-+IN)") (class "Default")
      (node (ref "C3") (pin "2") (pinfunction "2_2") (pintype "passive"))
      (node (ref "IC4") (pin "10") (pinfunction "+IN_10") (pintype "input"))
      (node (ref "R10") (pin "2") (pinfunction "2_2") (pintype "passive"))
      (node (ref "R9") (pin "2") (pinfunction "2_2") (pintype "passive"))
    )
    (net (code "36") (name "Net-(IC4C--IN)") (class "Default")
      (node (ref "IC4") (pin "9") (pinfunction "-IN_9") (pintype "input"))
      (node (ref "R13") (pin "2") (pinfunction "2_2") (pintype "passive"))
      (node (ref "R14") (pin "1") (pinfunction "1_1") (pintype "passive"))
    )
    (net (code "37") (name "Net-(IC4C-OUT)") (class "Default")
      (node (ref "IC4") (pin "12") (pinfunction "+IN_12") (pintype "input"))
      (node (ref "IC4") (pin "8") (pinfunction "OUT_8") (pintype "output"))
      (node (ref "R14") (pin "2") (pinfunction "2_2") (pintype "passive"))
    )
    (net (code "38") (name "Net-(IC4D--IN)") (class "Default")
      (node (ref "IC4") (pin "13") (pinfunction "-IN_13") (pintype "input"))
      (node (ref "Q3") (pin "1") (pinfunction "E_1") (pintype "passive"))
      (node (ref "Q4") (pin "1") (pinfunction "E_1") (pintype "passive"))
      (node (ref "R15") (pin "2") (pinfunction "2_2") (pintype "passive"))
      (node (ref "R16") (pin "1") (pinfunction "1_1") (pintype "passive"))
    )
    (net (code "39") (name "Net-(IC4D-OUT)") (class "Default")
      (node (ref "IC4") (pin "14") (pinfunction "OUT_14") (pintype "output"))
      (node (ref "Q3") (pin "2") (pinfunction "B_2") (pintype "passive"))
      (node (ref "Q4") (pin "2") (pinfunction "B_2") (pintype "passive"))
      (node (ref "R15") (pin "1") (pinfunction "1_1") (pintype "passive"))
    )
    (net (code "40") (name "Net-(IC5A-+IN)") (class "Default")
      (node (ref "C5") (pin "2") (pinfunction "2_2") (pintype "passive"))
      (node (ref "IC5") (pin "3") (pinfunction "+IN_3") (pintype "input"))
      (node (ref "R17") (pin "2") (pinfunction "2_2") (pintype "passive"))
    )
    (net (code "41") (name "Net-(IC5A--IN)") (class "Default")
      (node (ref "IC5") (pin "2") (pinfunction "-IN_2") (pintype "input"))
      (node (ref "R18") (pin "2") (pinfunction "2_2") (pintype "passive"))
      (node (ref "R19") (pin "1") (pinfunction "1_1") (pintype "passive"))
    )
    (net (code "42") (name "Net-(IC5A-OUT)") (class "Default")
      (node (ref "IC5") (pin "1") (pinfunction "OUT_1") (pintype "output"))
      (node (ref "IC5") (pin "5") (pinfunction "+IN_5") (pintype "input"))
      (node (ref "R19") (pin "2") (pinfunction "2_2") (pintype "passive"))
    )
    (net (code "43") (name "Net-(IC5B--IN)") (class "Default")
      (node (ref "IC5") (pin "6") (pinfunction "-IN_6") (pintype "input"))
      (node (ref "Q5") (pin "G") (pinfunction "E_G") (pintype "passive"))
      (node (ref "R22") (pin "1") (pinfunction "1_1") (pintype "passive"))
      (node (ref "R23") (pin "2") (pinfunction "2_2") (pintype "passive"))
    )
    (net (code "44") (name "Net-(IC5B-OUT)") (class "Default")
      (node (ref "IC5") (pin "7") (pinfunction "OUT_7") (pintype "output"))
      (node (ref "Q6") (pin "2") (pinfunction "B_2") (pintype "passive"))
    )
    (net (code "45") (name "Net-(IC5C-+IN)") (class "Default")
      (node (ref "IC5") (pin "10") (pinfunction "+IN_10") (pintype "input"))
      (node (ref "R21") (pin "1") (pinfunction "1_1") (pintype "passive"))
      (node (ref "R22") (pin "2") (pinfunction "2_2") (pintype "passive"))
    )
    (net (code "46") (name "Net-(IC5C--IN)") (class "Default")
      (node (ref "IC5") (pin "9") (pinfunction "-IN_9") (pintype "input"))
      (node (ref "Q7") (pin "E") (pinfunction "E_E") (pintype "passive"))
      (node (ref "R23") (pin "1") (pinfunction "1_1") (pintype "passive"))
    )
    (net (code "47") (name "Net-(IC5C-OUT)") (class "Default")
      (node (ref "IC5") (pin "8") (pinfunction "OUT_8") (pintype "output"))
      (node (ref "Q7") (pin "B") (pinfunction "B_B") (pintype "passive"))
    )
    (net (code "48") (name "Net-(IC6-3V3OUT)") (class "Default")
      (node (ref "C11") (pin "1") (pinfunction "1_1") (pintype "passive"))
      (node (ref "IC6") (pin "17") (pinfunction "3V3OUT_17") (pintype "output"))
    )
    (net (code "49") (name "Net-(IC6-CBUS0)") (class "Default")
      (node (ref "IC6") (pin "23") (pinfunction "CBUS0_23") (pintype "bidirectional"))
      (node (ref "LED1") (pin "4") (pinfunction "C_4") (pintype "passive"))
    )
    (net (code "50") (name "Net-(IC6-CBUS1)") (class "Default")
      (node (ref "IC6") (pin "22") (pinfunction "CBUS1_22") (pintype "bidirectional"))
      (node (ref "LED1") (pin "1") (pinfunction "C_1") (pintype "passive"))
    )
    (net (code "51") (name "Net-(IC6-USBDM)") (class "Default")
      (node (ref "IC6") (pin "16") (pinfunction "USBDM_16") (pintype "bidirectional"))
      (node (ref "X3") (pin "2") (pinfunction "2_2") (pintype "passive"))
    )
    (net (code "52") (name "Net-(IC6-USBDP)") (class "Default")
      (node (ref "IC6") (pin "15") (pinfunction "USBDP_15") (pintype "bidirectional"))
      (node (ref "X3") (pin "3") (pinfunction "3_3") (pintype "passive"))
    )
    (net (code "53") (name "Net-(JP1-Pad3)") (class "Default")
      (node (ref "JP1") (pin "3") (pinfunction "3_3") (pintype "passive"))
      (node (ref "R39") (pin "1") (pinfunction "1_1") (pintype "passive"))
      (node (ref "R43") (pin "1") (pinfunction "1_1") (pintype "passive"))
    )
    (net (code "54") (name "Net-(JP1-Pad5)") (class "Default")
      (node (ref "JP1") (pin "5") (pinfunction "5_5") (pintype "passive"))
      (node (ref "R40") (pin "1") (pinfunction "1_1") (pintype "passive"))
      (node (ref "R44") (pin "1") (pinfunction "1_1") (pintype "passive"))
    )
    (net (code "55") (name "Net-(JP1-Pad6)") (class "Default")
      (node (ref "JP1") (pin "6") (pinfunction "6_6") (pintype "passive"))
      (node (ref "R42") (pin "1") (pinfunction "1_1") (pintype "passive"))
      (node (ref "R46") (pin "1") (pinfunction "1_1") (pintype "passive"))
    )
    (net (code "56") (name "Net-(JP1-Pad7)") (class "Default")
      (node (ref "JP1") (pin "7") (pinfunction "7_7") (pintype "passive"))
      (node (ref "R41") (pin "1") (pinfunction "1_1") (pintype "passive"))
      (node (ref "R45") (pin "1") (pinfunction "1_1") (pintype "passive"))
    )
    (net (code "57") (name "Net-(LED1A-A)") (class "Default")
      (node (ref "LED1") (pin "2") (pinfunction "A_2") (pintype "passive"))
      (node (ref "R32") (pin "1") (pinfunction "1_1") (pintype "passive"))
    )
    (net (code "58") (name "Net-(LED1B-A)") (class "Default")
      (node (ref "LED1") (pin "3") (pinfunction "A_3") (pintype "passive"))
      (node (ref "R31") (pin "1") (pinfunction "1_1") (pintype "passive"))
    )
    (net (code "59") (name "Net-(LED2-PadA)") (class "Default")
      (node (ref "LED2") (pin "A") (pinfunction "A_A") (pintype "passive"))
      (node (ref "R33") (pin "1") (pinfunction "1_1") (pintype "passive"))
    )
    (net (code "60") (name "Net-(OUT1-P)") (class "Default")
      (node (ref "OUT1") (pin "1") (pinfunction "P_1") (pintype "passive"))
      (node (ref "R8") (pin "2") (pinfunction "2_2") (pintype "passive"))
    )
    (net (code "61") (name "Net-(OUT2-P)") (class "Default")
      (node (ref "OUT2") (pin "1") (pinfunction "P_1") (pintype "passive"))
      (node (ref "R16") (pin "2") (pinfunction "2_2") (pintype "passive"))
    )
    (net (code "62") (name "Net-(OUT3-P)") (class "Default")
      (node (ref "OUT3") (pin "1") (pinfunction "P_1") (pintype "passive"))
      (node (ref "R21") (pin "2") (pinfunction "2_2") (pintype "passive"))
      (node (ref "R25") (pin "2") (pinfunction "2_2") (pintype "passive"))
    )
    (net (code "63") (name "Net-(Q5-B)") (class "Default")
      (node (ref "Q5") (pin "T1") (pinfunction "B_T1") (pintype "passive"))
      (node (ref "Q6") (pin "1") (pinfunction "E_1") (pintype "passive"))
    )
    (net (code "64") (name "Net-(R3-Pad2)") (class "Default")
      (node (ref "R3") (pin "2") (pinfunction "2_2") (pintype "passive"))
      (node (ref "R4") (pin "2") (pinfunction "2_2") (pintype "passive"))
      (node (ref "R5") (pin "1") (pinfunction "1_1") (pintype "passive"))
    )
    (net (code "65") (name "Net-(R11-Pad2)") (class "Default")
      (node (ref "R11") (pin "2") (pinfunction "2_2") (pintype "passive"))
      (node (ref "R12") (pin "2") (pinfunction "2_2") (pintype "passive"))
      (node (ref "R13") (pin "1") (pinfunction "1_1") (pintype "passive"))
    )
    (net (code "66") (name "PS_CUR") (class "Default")
      (node (ref "IC1") (pin "40") (pinfunction "(ADC0)PA0_40") (pintype "bidirectional"))
      (node (ref "Q7") (pin "C") (pinfunction "C_C") (pintype "passive"))
      (node (ref "R24") (pin "2") (pinfunction "2_2") (pintype "passive"))
    )
    (net (code "67") (name "PS_VOLT") (class "Default")
      (node (ref "IC1") (pin "39") (pinfunction "(ADC1)PA1_39") (pintype "bidirectional"))
      (node (ref "R25") (pin "1") (pinfunction "1_1") (pintype "passive"))
      (node (ref "R26") (pin "2") (pinfunction "2_2") (pintype "passive"))
    )
    (net (code "68") (name "RST") (class "Default")
      (node (ref "IC1") (pin "9") (pinfunction "RESET_9") (pintype "input"))
      (node (ref "SV1") (pin "5") (pinfunction "5_5") (pintype "passive"))
    )
    (net (code "69") (name "SCK") (class "Default")
      (node (ref "IC1") (pin "8") (pinfunction "(SCK)PB7_8") (pintype "bidirectional"))
      (node (ref "IC2") (pin "4") (pinfunction "SCK_4") (pintype "input"))
      (node (ref "IC3") (pin "3") (pinfunction "SCK_3") (pintype "input"))
      (node (ref "JP1") (pin "10") (pinfunction "10_10") (pintype "passive"))
      (node (ref "JP2") (pin "2") (pinfunction "2_2") (pintype "passive"))
      (node (ref "R41") (pin "2") (pinfunction "2_2") (pintype "passive"))
      (node (ref "SV1") (pin "7") (pinfunction "7_7") (pintype "passive"))
    )
    (net (code "70") (name "TS_IRQ") (class "Default")
      (node (ref "IC1") (pin "38") (pinfunction "(ADC2)PA2_38") (pintype "bidirectional"))
      (node (ref "JP1") (pin "14") (pinfunction "14_14") (pintype "passive"))
    )
    (net (code "71") (name "USB_RX") (class "Default")
      (node (ref "IC1") (pin "14") (pinfunction "(RXD)PD0_14") (pintype "bidirectional"))
      (node (ref "IC6") (pin "1") (pinfunction "TXD_1") (pintype "output"))
    )
    (net (code "72") (name "USB_TX") (class "Default")
      (node (ref "IC1") (pin "15") (pinfunction "(TXD)PD1_15") (pintype "bidirectional"))
      (node (ref "IC6") (pin "5") (pinfunction "RXD_5") (pintype "input"))
    )
    (net (code "73") (name "unconnected-(IC5D-+IN-Pad12)") (class "Default")
      (node (ref "IC5") (pin "12") (pinfunction "+IN_12") (pintype "input"))
    )
    (net (code "74") (name "unconnected-(IC5D--IN-Pad13)") (class "Default")
      (node (ref "IC5") (pin "13") (pinfunction "-IN_13") (pintype "input"))
    )
    (net (code "75") (name "unconnected-(IC5D-OUT-Pad14)") (class "Default")
      (node (ref "IC5") (pin "14") (pinfunction "OUT_14") (pintype "output"))
    )
    (net (code "76") (name "unconnected-(IC6-CBUS2-Pad13)") (class "Default")
      (node (ref "IC6") (pin "13") (pinfunction "CBUS2_13") (pintype "bidirectional"))
    )
    (net (code "77") (name "unconnected-(IC6-CBUS3-Pad14)") (class "Default")
      (node (ref "IC6") (pin "14") (pinfunction "CBUS3_14") (pintype "bidirectional"))
    )
    (net (code "78") (name "unconnected-(IC6-CBUS4-Pad12)") (class "Default")
      (node (ref "IC6") (pin "12") (pinfunction "CBUS4_12") (pintype "bidirectional"))
    )
    (net (code "79") (name "unconnected-(IC6-OSCI-Pad27)") (class "Default")
      (node (ref "IC6") (pin "27") (pinfunction "OSCI_27") (pintype "input"))
    )
    (net (code "80") (name "unconnected-(IC6-OSCO-Pad28)") (class "Default")
      (node (ref "IC6") (pin "28") (pinfunction "OSCO_28") (pintype "output"))
    )
    (net (code "81") (name "unconnected-(IC6-~{CTS}-Pad11)") (class "Default")
      (node (ref "IC6") (pin "11") (pinfunction "~{CTS}_11") (pintype "input"))
    )
    (net (code "82") (name "unconnected-(IC6-~{DCD}-Pad10)") (class "Default")
      (node (ref "IC6") (pin "10") (pinfunction "~{DCD}_10") (pintype "input"))
    )
    (net (code "83") (name "unconnected-(IC6-~{DSR}-Pad9)") (class "Default")
      (node (ref "IC6") (pin "9") (pinfunction "~{DSR}_9") (pintype "input"))
    )
    (net (code "84") (name "unconnected-(IC6-~{DTR}-Pad2)") (class "Default")
      (node (ref "IC6") (pin "2") (pinfunction "~{DTR}_2") (pintype "output"))
    )
    (net (code "85") (name "unconnected-(IC6-~{RESET}-Pad19)") (class "Default")
      (node (ref "IC6") (pin "19") (pinfunction "~{RESET}_19") (pintype "input"))
    )
    (net (code "86") (name "unconnected-(IC6-~{RI}-Pad6)") (class "Default")
      (node (ref "IC6") (pin "6") (pinfunction "~{RI}_6") (pintype "input"))
    )
    (net (code "87") (name "unconnected-(IC6-~{RTS}-Pad3)") (class "Default")
      (node (ref "IC6") (pin "3") (pinfunction "~{RTS}_3") (pintype "output"))
    )
    (net (code "88") (name "unconnected-(JP1-Pad9)") (class "Default")
      (node (ref "JP1") (pin "9") (pinfunction "9_9") (pintype "passive"))
    )
    (net (code "89") (name "unconnected-(SV1-Pad3)") (class "Default")
      (node (ref "SV1") (pin "3") (pinfunction "3_3") (pintype "passive"))
    )
    (net (code "90") (name "unconnected-(SV2-Pad14)") (class "Default")
      (node (ref "SV2") (pin "14") (pinfunction "14_14") (pintype "passive"))
    )
    (net (code "91") (name "unconnected-(U$2-D+(B)-PadP$6)") (class "Default")
      (node (ref "U$2") (pin "P$6") (pinfunction "D+(B)_P$6") (pintype "bidirectional"))
    )
    (net (code "92") (name "unconnected-(U$2-D+-PadP$8)") (class "Default")
      (node (ref "U$2") (pin "P$8") (pinfunction "D+_P$8") (pintype "bidirectional"))
    )
    (net (code "93") (name "unconnected-(U$2-D-(B)-PadP$5)") (class "Default")
      (node (ref "U$2") (pin "P$5") (pinfunction "D-(B)_P$5") (pintype "bidirectional"))
    )
    (net (code "94") (name "unconnected-(U$2-D--PadP$7)") (class "Default")
      (node (ref "U$2") (pin "P$7") (pinfunction "D-_P$7") (pintype "bidirectional"))
    )
    (net (code "95") (name "~{DDS_CS}") (class "Default")
      (node (ref "IC1") (pin "4") (pinfunction "(AIN1/OC0)PB3_4") (pintype "bidirectional"))
      (node (ref "IC2") (pin "3") (pinfunction "~{CS}_3") (pintype "input"))
    )
    (net (code "96") (name "~{IO_EXP_CS}") (class "Default")
      (node (ref "IC1") (pin "3") (pinfunction "(AIN0/INT2)PB2_3") (pintype "bidirectional"))
      (node (ref "JP2") (pin "5") (pinfunction "5_5") (pintype "passive"))
    )
    (net (code "97") (name "~{LCD_CS}") (class "Default")
      (node (ref "IC1") (pin "2") (pinfunction "(T1)PB1_2") (pintype "bidirectional"))
      (node (ref "R39") (pin "2") (pinfunction "2_2") (pintype "passive"))
    )
    (net (code "98") (name "~{PS_CS}") (class "Default")
      (node (ref "IC1") (pin "5") (pinfunction "(SS)PB4_5") (pintype "bidirectional"))
      (node (ref "IC3") (pin "2") (pinfunction "~{CS}_2") (pintype "input"))
    )
    (net (code "99") (name "~{TS_CS}") (class "Default")
      (node (ref "IC1") (pin "37") (pinfunction "(ADC3)PA3_37") (pintype "bidirectional"))
      (node (ref "JP1") (pin "11") (pinfunction "11_11") (pintype "passive"))
    )
  )
)
